# GCM_SCH_STM32.net
KiCad netlist of a schematic drawn in Altium Designer
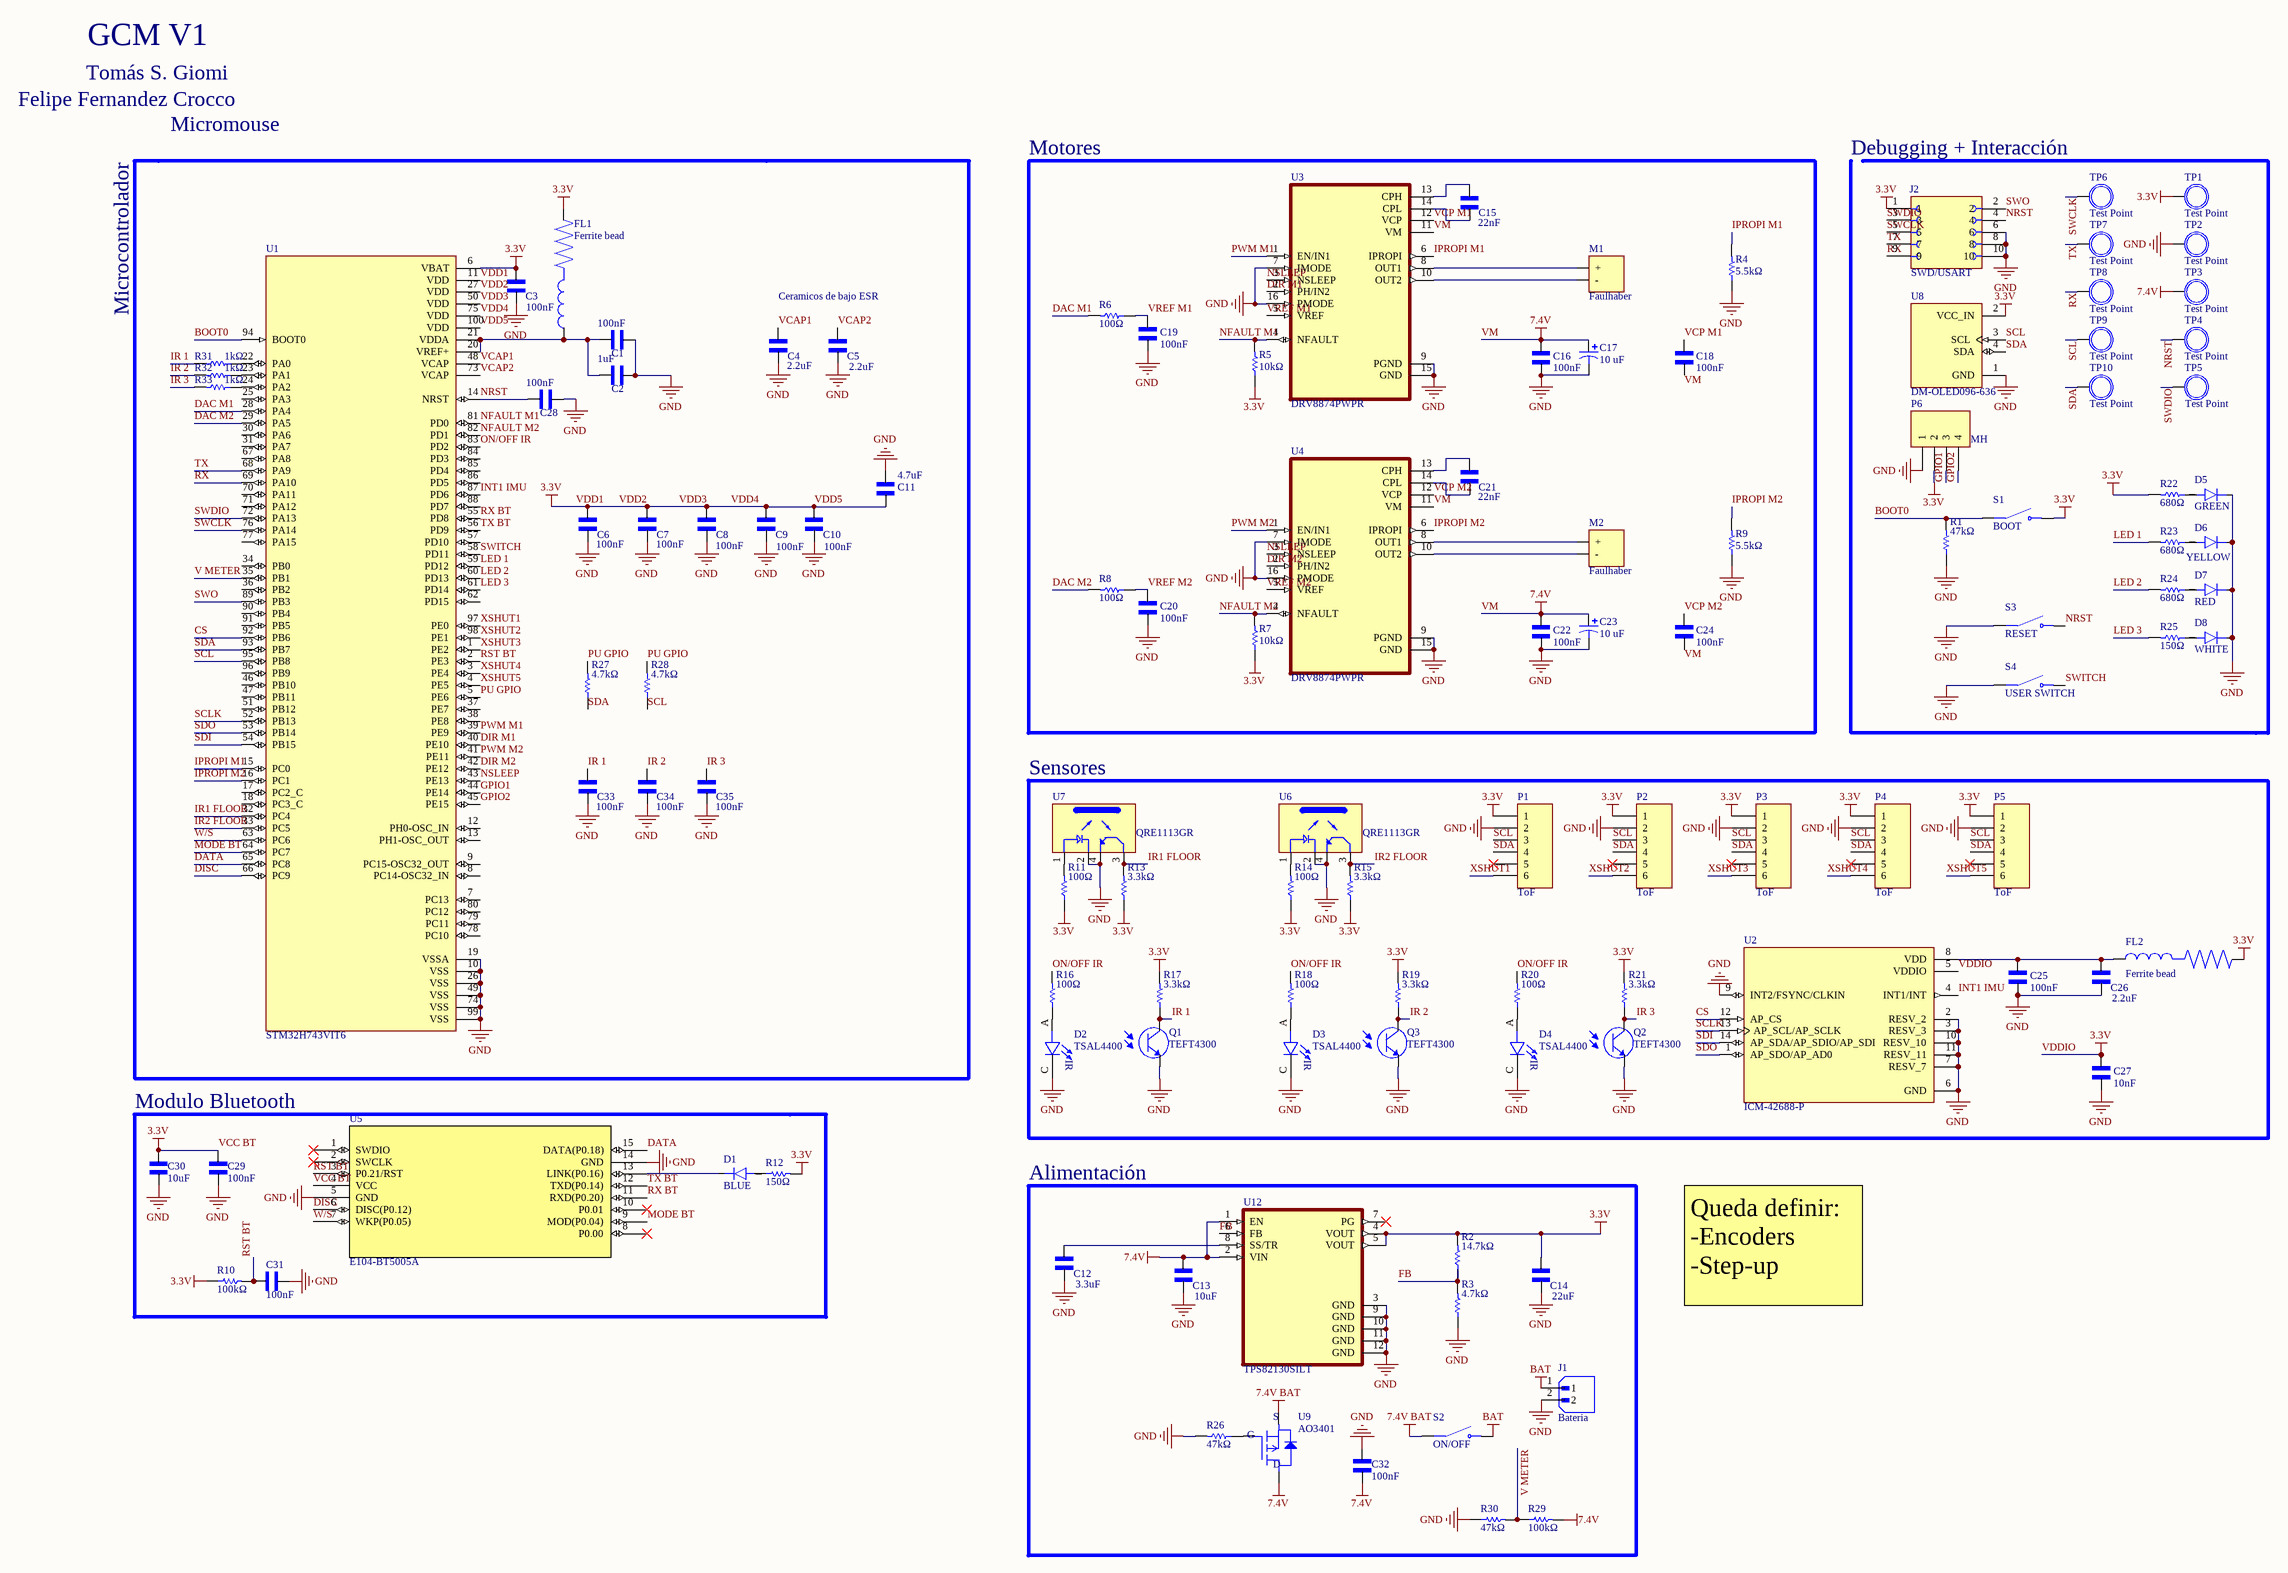
[diagram p0: GCM_SCH_STM32.SchDoc]

(export (version "E")
  (design (tool "Eeschema 10.0.6"))
  (components
    (comp (ref "C1")
      (value "100nF")
      (footprint "CAPACITOR TANTALIO")
      (description "0805")
      (fields (field (name "MP") "GRM035R60J475ME15D") (field (name "MF") "Murata"))
      (libsource (lib "") (part "CAPACITOR TANTALIO_1"))
    )
    (comp (ref "C2")
      (value "1uF")
      (footprint "CAPACITOR TANTALIO")
      (description "0805")
      (fields (field (name "MP") "GRM035R60J475ME15D") (field (name "MF") "Murata"))
      (libsource (lib "") (part "CAPACITOR TANTALIO_1"))
    )
    (comp (ref "C3")
      (value "100nF")
      (footprint "CAPACITOR TANTALIO")
      (description "0805")
      (fields (field (name "MP") "GRM035R60J475ME15D") (field (name "MF") "Murata"))
      (libsource (lib "GCMLibreriasSCH") (part "CAPACITOR TANTALIO"))
    )
    (comp (ref "C4")
      (value "2.2uF")
      (footprint "CAPACITOR TANTALIO")
      (description "0805")
      (fields (field (name "MP") "GRM035R60J475ME15D") (field (name "MF") "Murata"))
      (libsource (lib "GCMLibreriasSCH") (part "CAPACITOR TANTALIO"))
    )
    (comp (ref "C5")
      (value "2.2uF")
      (footprint "CAPACITOR TANTALIO")
      (description "0805")
      (fields (field (name "MP") "GRM035R60J475ME15D") (field (name "MF") "Murata"))
      (libsource (lib "GCMLibreriasSCH") (part "CAPACITOR TANTALIO"))
    )
    (comp (ref "C6")
      (value "100nF")
      (footprint "CAPACITOR TANTALIO")
      (description "0805")
      (fields (field (name "MP") "GRM035R60J475ME15D") (field (name "MF") "Murata"))
      (libsource (lib "GCMLibreriasSCH") (part "CAPACITOR TANTALIO"))
    )
    (comp (ref "C7")
      (value "100nF")
      (footprint "CAPACITOR TANTALIO")
      (description "0805")
      (fields (field (name "MP") "GRM035R60J475ME15D") (field (name "MF") "Murata"))
      (libsource (lib "GCMLibreriasSCH") (part "CAPACITOR TANTALIO"))
    )
    (comp (ref "C8")
      (value "100nF")
      (footprint "CAPACITOR TANTALIO")
      (description "0805")
      (fields (field (name "MP") "GRM035R60J475ME15D") (field (name "MF") "Murata"))
      (libsource (lib "GCMLibreriasSCH") (part "CAPACITOR TANTALIO"))
    )
    (comp (ref "C9")
      (value "100nF")
      (footprint "CAPACITOR TANTALIO")
      (description "0805")
      (fields (field (name "MP") "GRM035R60J475ME15D") (field (name "MF") "Murata"))
      (libsource (lib "GCMLibreriasSCH") (part "CAPACITOR TANTALIO"))
    )
    (comp (ref "C10")
      (value "100nF")
      (footprint "CAPACITOR TANTALIO")
      (description "0805")
      (fields (field (name "MP") "GRM035R60J475ME15D") (field (name "MF") "Murata"))
      (libsource (lib "GCMLibreriasSCH") (part "CAPACITOR TANTALIO"))
    )
    (comp (ref "C11")
      (value "4.7uF")
      (footprint "CAPACITOR TANTALIO")
      (description "0805")
      (fields (field (name "MP") "GRM035R60J475ME15D") (field (name "MF") "Murata"))
      (libsource (lib "GCMLibreriasSCH") (part "CAPACITOR TANTALIO"))
    )
    (comp (ref "C12")
      (value "3.3uF")
      (footprint "CAPACITOR TANTALIO")
      (description "0805")
      (fields (field (name "MP") "GRM035R60J475ME15D") (field (name "MF") "Murata"))
      (libsource (lib "GCMLibreriasSCH") (part "CAPACITOR TANTALIO"))
    )
    (comp (ref "C13")
      (value "10uF")
      (footprint "CAPACITOR TANTALIO")
      (description "0805")
      (fields (field (name "MP") "GRM035R60J475ME15D") (field (name "MF") "Murata"))
      (libsource (lib "GCMLibreriasSCH") (part "CAPACITOR TANTALIO"))
    )
    (comp (ref "C14")
      (value "22uF")
      (footprint "CAPACITOR TANTALIO")
      (description "0805")
      (fields (field (name "MP") "GRM035R60J475ME15D") (field (name "MF") "Murata"))
      (libsource (lib "GCMLibreriasSCH") (part "CAPACITOR TANTALIO"))
    )
    (comp (ref "C15")
      (value "22nF")
      (footprint "CAPACITOR TANTALIO")
      (description "0805")
      (fields (field (name "MP") "GRM035R60J475ME15D") (field (name "MF") "Murata"))
      (libsource (lib "GCMLibreriasSCH") (part "CAPACITOR TANTALIO"))
    )
    (comp (ref "C16")
      (value "100nF")
      (footprint "CAPACITOR TANTALIO")
      (description "0805")
      (fields (field (name "MP") "GRM035R60J475ME15D") (field (name "MF") "Murata"))
      (libsource (lib "GCMLibreriasSCH") (part "CAPACITOR TANTALIO"))
    )
    (comp (ref "C17")
      (value "10 uF")
      (footprint "Cap El 10uF")
      (libsource (lib "GCMLibreriasSCH") (part "Cap el 10 uF"))
    )
    (comp (ref "C18")
      (value "100nF")
      (footprint "CAPACITOR TANTALIO")
      (description "0805")
      (fields (field (name "MP") "GRM035R60J475ME15D") (field (name "MF") "Murata"))
      (libsource (lib "GCMLibreriasSCH") (part "CAPACITOR TANTALIO"))
    )
    (comp (ref "C19")
      (value "100nF")
      (footprint "CAPACITOR TANTALIO")
      (description "0805")
      (fields (field (name "MP") "GRM035R60J475ME15D") (field (name "MF") "Murata"))
      (libsource (lib "GCMLibreriasSCH") (part "CAPACITOR TANTALIO"))
    )
    (comp (ref "C20")
      (value "100nF")
      (footprint "CAPACITOR TANTALIO")
      (description "0805")
      (fields (field (name "MP") "GRM035R60J475ME15D") (field (name "MF") "Murata"))
      (libsource (lib "GCMLibreriasSCH") (part "CAPACITOR TANTALIO"))
    )
    (comp (ref "C21")
      (value "22nF")
      (footprint "CAPACITOR TANTALIO")
      (description "0805")
      (fields (field (name "MP") "GRM035R60J475ME15D") (field (name "MF") "Murata"))
      (libsource (lib "GCMLibreriasSCH") (part "CAPACITOR TANTALIO"))
    )
    (comp (ref "C22")
      (value "100nF")
      (footprint "CAPACITOR TANTALIO")
      (description "0805")
      (fields (field (name "MP") "GRM035R60J475ME15D") (field (name "MF") "Murata"))
      (libsource (lib "GCMLibreriasSCH") (part "CAPACITOR TANTALIO"))
    )
    (comp (ref "C23")
      (value "10 uF")
      (footprint "Cap El 10uF")
      (libsource (lib "GCMLibreriasSCH") (part "Cap el 10 uF"))
    )
    (comp (ref "C24")
      (value "100nF")
      (footprint "CAPACITOR TANTALIO")
      (description "0805")
      (fields (field (name "MP") "GRM035R60J475ME15D") (field (name "MF") "Murata"))
      (libsource (lib "GCMLibreriasSCH") (part "CAPACITOR TANTALIO"))
    )
    (comp (ref "C25")
      (value "100nF")
      (footprint "CAPACITOR TANTALIO")
      (description "0805")
      (fields (field (name "MP") "GRM035R60J475ME15D") (field (name "MF") "Murata"))
      (libsource (lib "GCMLibreriasSCH") (part "CAPACITOR TANTALIO"))
    )
    (comp (ref "C26")
      (value "2.2uF")
      (footprint "CAPACITOR TANTALIO")
      (description "0805")
      (fields (field (name "MP") "GRM035R60J475ME15D") (field (name "MF") "Murata"))
      (libsource (lib "GCMLibreriasSCH") (part "CAPACITOR TANTALIO"))
    )
    (comp (ref "C27")
      (value "10nF")
      (footprint "CAPACITOR TANTALIO")
      (description "0805")
      (fields (field (name "MP") "GRM035R60J475ME15D") (field (name "MF") "Murata"))
      (libsource (lib "GCMLibreriasSCH") (part "CAPACITOR TANTALIO"))
    )
    (comp (ref "C28")
      (value "100nF")
      (footprint "CAPACITOR TANTALIO")
      (description "0805")
      (fields (field (name "MP") "GRM035R60J475ME15D") (field (name "MF") "Murata"))
      (libsource (lib "") (part "CAPACITOR TANTALIO_1"))
    )
    (comp (ref "C29")
      (value "100nF")
      (footprint "CAPACITOR TANTALIO")
      (description "0805")
      (fields (field (name "MP") "GRM035R60J475ME15D") (field (name "MF") "Murata"))
      (libsource (lib "GCMLibreriasSCH") (part "CAPACITOR TANTALIO"))
    )
    (comp (ref "C30")
      (value "10uF")
      (footprint "CAPACITOR TANTALIO")
      (description "0805")
      (fields (field (name "MP") "GRM035R60J475ME15D") (field (name "MF") "Murata"))
      (libsource (lib "GCMLibreriasSCH") (part "CAPACITOR TANTALIO"))
    )
    (comp (ref "C31")
      (value "100nF")
      (footprint "CAPACITOR TANTALIO")
      (description "0805")
      (fields (field (name "MP") "GRM035R60J475ME15D") (field (name "MF") "Murata"))
      (libsource (lib "") (part "CAPACITOR TANTALIO_3"))
    )
    (comp (ref "C32")
      (value "100nF")
      (footprint "CAPACITOR TANTALIO")
      (description "0805")
      (fields (field (name "MP") "GRM035R60J475ME15D") (field (name "MF") "Murata"))
      (libsource (lib "") (part "CAPACITOR TANTALIO_2"))
    )
    (comp (ref "C33")
      (value "100nF")
      (footprint "CAPACITOR TANTALIO")
      (description "0805")
      (fields (field (name "MP") "GRM035R60J475ME15D") (field (name "MF") "Murata"))
      (libsource (lib "GCMLibreriasSCH") (part "CAPACITOR TANTALIO"))
    )
    (comp (ref "C34")
      (value "100nF")
      (footprint "CAPACITOR TANTALIO")
      (description "0805")
      (fields (field (name "MP") "GRM035R60J475ME15D") (field (name "MF") "Murata"))
      (libsource (lib "GCMLibreriasSCH") (part "CAPACITOR TANTALIO"))
    )
    (comp (ref "C35")
      (value "100nF")
      (footprint "CAPACITOR TANTALIO")
      (description "0805")
      (fields (field (name "MP") "GRM035R60J475ME15D") (field (name "MF") "Murata"))
      (libsource (lib "GCMLibreriasSCH") (part "CAPACITOR TANTALIO"))
    )
    (comp (ref "D1")
      (value "BLUE")
      (footprint "LED SMD")
      (description "0805")
      (fields (field (name "MP") "597-5311-402F"))
      (libsource (lib "GCMLibreriasSCH") (part "LED SMD"))
    )
    (comp (ref "D2")
      (value "TSAL4400")
      (footprint "GCMLibreriasPCB:LEDRD254W45D335H610")
      (description "Infrared Emitter 940nm 36mW/sr Circular Top Mount 2-Pin T-1 Bulk")
      (fields (field (name "MF") "Vishay Semiconductor"))
      (libsource (lib "GCMLibreriasSCH") (part "TSAL4400"))
    )
    (comp (ref "D3")
      (value "TSAL4400")
      (footprint "GCMLibreriasPCB:LEDRD254W45D335H610")
      (description "Infrared Emitter 940nm 36mW/sr Circular Top Mount 2-Pin T-1 Bulk")
      (fields (field (name "MF") "Vishay Semiconductor"))
      (libsource (lib "GCMLibreriasSCH") (part "TSAL4400"))
    )
    (comp (ref "D4")
      (value "TSAL4400")
      (footprint "GCMLibreriasPCB:LEDRD254W45D335H610")
      (description "Infrared Emitter 940nm 36mW/sr Circular Top Mount 2-Pin T-1 Bulk")
      (fields (field (name "MF") "Vishay Semiconductor"))
      (libsource (lib "GCMLibreriasSCH") (part "TSAL4400"))
    )
    (comp (ref "D5")
      (value "GREEN")
      (footprint "LED SMD")
      (description "0805")
      (fields (field (name "MP") "597-5311-402F"))
      (libsource (lib "GCMLibreriasSCH") (part "LED SMD"))
    )
    (comp (ref "D6")
      (value "YELLOW")
      (footprint "LED SMD")
      (description "0805")
      (fields (field (name "MP") "597-5311-402F"))
      (libsource (lib "GCMLibreriasSCH") (part "LED SMD"))
    )
    (comp (ref "D7")
      (value "RED")
      (footprint "LED SMD")
      (description "0805")
      (fields (field (name "MP") "597-5311-402F"))
      (libsource (lib "GCMLibreriasSCH") (part "LED SMD"))
    )
    (comp (ref "D8")
      (value "WHITE")
      (footprint "LED SMD")
      (description "0805")
      (fields (field (name "MP") "597-5311-402F"))
      (libsource (lib "GCMLibreriasSCH") (part "LED SMD"))
    )
    (comp (ref "FL1")
      (value "Ferrite bead")
      (footprint "BEADC1608X95N")
      (description "600 Ohms @ 100 MHz 1 - Ferrite Bead 0603 (1608 Metric) 500mA 380mOhm")
      (fields (field (name "MF") "Murata") (field (name "MP") "BLM18AG601SN1D"))
      (libsource (lib "GCMLibreriasSCH") (part "BLM18AG601SN1D"))
    )
    (comp (ref "FL2")
      (value "Ferrite bead")
      (footprint "BEADC1608X95N")
      (description "600 Ohms @ 100 MHz 1 - Ferrite Bead 0603 (1608 Metric) 500mA 380mOhm")
      (fields (field (name "MF") "Murata") (field (name "MP") "BLM18AG601SN1D"))
      (libsource (lib "GCMLibreriasSCH") (part "BLM18AG601SN1D"))
    )
    (comp (ref "J1")
      (value "Bateria")
      (footprint "JST_B2B-XH-A")
      (fields
        (field (name "MF") "{'manufacturer': u'JST Sales America Inc.'}")
        (field (name "MP") "B2B-XH-A")
      )
      (libsource (lib "GCMLibreriasSCH") (part "B2B-XH-A"))
    )
    (comp (ref "J2")
      (value "SWD/USART")
      (footprint "AMPHENOL_20021311-00026T4LF")
      (fields (field (name "MF") "Amphenol ICC") (field (name "MP") "20021311-00026T4LF"))
      (libsource (lib "GCMLibreriasSCH") (part "20021311-00026T4LF"))
    )
    (comp (ref "M1")
      (value "Faulhaber")
      (footprint "MOTOR")
      (fields (field (name "PUBLISHER") "Altium Limited"))
      (libsource (lib "GCMLibreriasSCH") (part "Faulhaber"))
    )
    (comp (ref "M2")
      (value "Faulhaber")
      (footprint "MOTOR")
      (fields (field (name "PUBLISHER") "Altium Limited"))
      (libsource (lib "GCMLibreriasSCH") (part "Faulhaber"))
    )
    (comp (ref "P1")
      (value "ToF")
      (footprint "FHDR1X6")
      (fields (field (name "PUBLISHER") "Altium Limited"))
      (libsource (lib "GCMLibreriasSCH") (part "FHeader 6X1"))
    )
    (comp (ref "P2")
      (value "ToF")
      (footprint "FHDR1X6")
      (fields (field (name "PUBLISHER") "Altium Limited"))
      (libsource (lib "GCMLibreriasSCH") (part "FHeader 6X1"))
    )
    (comp (ref "P3")
      (value "ToF")
      (footprint "FHDR1X6")
      (fields (field (name "PUBLISHER") "Altium Limited"))
      (libsource (lib "GCMLibreriasSCH") (part "FHeader 6X1"))
    )
    (comp (ref "P4")
      (value "ToF")
      (footprint "FHDR1X6")
      (fields (field (name "PUBLISHER") "Altium Limited"))
      (libsource (lib "GCMLibreriasSCH") (part "FHeader 6X1"))
    )
    (comp (ref "P5")
      (value "ToF")
      (footprint "FHDR1X6")
      (fields (field (name "PUBLISHER") "Altium Limited"))
      (libsource (lib "GCMLibreriasSCH") (part "FHeader 6X1"))
    )
    (comp (ref "P6")
      (value "MH")
      (footprint "FHDR1X4")
      (fields (field (name "PUBLISHER") "Altium Limited"))
      (libsource (lib "GCMLibreriasSCH") (part "FHeader 4X1_1"))
    )
    (comp (ref "Q1")
      (value "TEFT4300")
      (footprint "XDCR_TEFT4300")
      (description "Phototransistors 925nm Top View Radial, 3mm Dia (T-1)")
      (fields (field (name "MF") "Vishay Semiconductor"))
      (libsource (lib "GCMLibreriasSCH") (part "TEFT4300"))
    )
    (comp (ref "Q2")
      (value "TEFT4300")
      (footprint "XDCR_TEFT4300")
      (description "Phototransistors 925nm Top View Radial, 3mm Dia (T-1)")
      (fields (field (name "MF") "Vishay Semiconductor"))
      (libsource (lib "GCMLibreriasSCH") (part "TEFT4300"))
    )
    (comp (ref "Q3")
      (value "TEFT4300")
      (footprint "XDCR_TEFT4300")
      (description "Phototransistors 925nm Top View Radial, 3mm Dia (T-1)")
      (fields (field (name "MF") "Vishay Semiconductor"))
      (libsource (lib "GCMLibreriasSCH") (part "TEFT4300"))
    )
    (comp (ref "R1")
      (value "47kΩ")
      (footprint "RESISTENCIA SMD")
      (description "0805")
      (fields (field (name "PUBLISHER") "Altium Limited"))
      (libsource (lib "GCMLibreriasSCH") (part "RESISTENCIA"))
    )
    (comp (ref "R2")
      (value "14.7kΩ")
      (footprint "RESISTENCIA SMD")
      (description "0805")
      (fields (field (name "PUBLISHER") "Altium Limited"))
      (libsource (lib "GCMLibreriasSCH") (part "RESISTENCIA"))
    )
    (comp (ref "R3")
      (value "4.7kΩ")
      (footprint "RESISTENCIA SMD")
      (description "0805")
      (fields (field (name "PUBLISHER") "Altium Limited"))
      (libsource (lib "GCMLibreriasSCH") (part "RESISTENCIA"))
    )
    (comp (ref "R4")
      (value "5.5kΩ")
      (footprint "RESISTENCIA SMD")
      (description "0805")
      (fields (field (name "PUBLISHER") "Altium Limited"))
      (libsource (lib "GCMLibreriasSCH") (part "RESISTENCIA"))
    )
    (comp (ref "R5")
      (value "10kΩ")
      (footprint "RESISTENCIA SMD")
      (description "0805")
      (fields (field (name "PUBLISHER") "Altium Limited"))
      (libsource (lib "GCMLibreriasSCH") (part "RESISTENCIA"))
    )
    (comp (ref "R6")
      (value "100Ω")
      (footprint "RESISTENCIA SMD")
      (description "0805")
      (fields (field (name "PUBLISHER") "Altium Limited"))
      (libsource (lib "GCMLibreriasSCH") (part "RESISTENCIA"))
    )
    (comp (ref "R7")
      (value "10kΩ")
      (footprint "RESISTENCIA SMD")
      (description "0805")
      (fields (field (name "PUBLISHER") "Altium Limited"))
      (libsource (lib "GCMLibreriasSCH") (part "RESISTENCIA"))
    )
    (comp (ref "R8")
      (value "100Ω")
      (footprint "RESISTENCIA SMD")
      (description "0805")
      (fields (field (name "PUBLISHER") "Altium Limited"))
      (libsource (lib "GCMLibreriasSCH") (part "RESISTENCIA"))
    )
    (comp (ref "R9")
      (value "5.5kΩ")
      (footprint "RESISTENCIA SMD")
      (description "0805")
      (fields (field (name "PUBLISHER") "Altium Limited"))
      (libsource (lib "GCMLibreriasSCH") (part "RESISTENCIA"))
    )
    (comp (ref "R10")
      (value "100kΩ")
      (footprint "RESISTENCIA SMD")
      (description "0805")
      (fields (field (name "PUBLISHER") "Altium Limited"))
      (libsource (lib "GCMLibreriasSCH") (part "RESISTENCIA"))
    )
    (comp (ref "R11")
      (value "100Ω")
      (footprint "RESISTENCIA SMD")
      (description "0805")
      (fields (field (name "PUBLISHER") "Altium Limited"))
      (libsource (lib "GCMLibreriasSCH") (part "RESISTENCIA"))
    )
    (comp (ref "R12")
      (value "150Ω")
      (footprint "RESISTENCIA SMD")
      (description "0805")
      (fields (field (name "PUBLISHER") "Altium Limited"))
      (libsource (lib "GCMLibreriasSCH") (part "RESISTENCIA"))
    )
    (comp (ref "R13")
      (value "3.3kΩ")
      (footprint "RESISTENCIA SMD")
      (description "0805")
      (fields (field (name "PUBLISHER") "Altium Limited"))
      (libsource (lib "GCMLibreriasSCH") (part "RESISTENCIA"))
    )
    (comp (ref "R14")
      (value "100Ω")
      (footprint "RESISTENCIA SMD")
      (description "0805")
      (fields (field (name "PUBLISHER") "Altium Limited"))
      (libsource (lib "GCMLibreriasSCH") (part "RESISTENCIA"))
    )
    (comp (ref "R15")
      (value "3.3kΩ")
      (footprint "RESISTENCIA SMD")
      (description "0805")
      (fields (field (name "PUBLISHER") "Altium Limited"))
      (libsource (lib "GCMLibreriasSCH") (part "RESISTENCIA"))
    )
    (comp (ref "R16")
      (value "100Ω")
      (footprint "RESISTENCIA SMD")
      (description "0805")
      (fields (field (name "PUBLISHER") "Altium Limited"))
      (libsource (lib "GCMLibreriasSCH") (part "RESISTENCIA"))
    )
    (comp (ref "R17")
      (value "3.3kΩ")
      (footprint "RESISTENCIA SMD")
      (description "0805")
      (fields (field (name "PUBLISHER") "Altium Limited"))
      (libsource (lib "GCMLibreriasSCH") (part "RESISTENCIA"))
    )
    (comp (ref "R18")
      (value "100Ω")
      (footprint "RESISTENCIA SMD")
      (description "0805")
      (fields (field (name "PUBLISHER") "Altium Limited"))
      (libsource (lib "GCMLibreriasSCH") (part "RESISTENCIA"))
    )
    (comp (ref "R19")
      (value "3.3kΩ")
      (footprint "RESISTENCIA SMD")
      (description "0805")
      (fields (field (name "PUBLISHER") "Altium Limited"))
      (libsource (lib "GCMLibreriasSCH") (part "RESISTENCIA"))
    )
    (comp (ref "R20")
      (value "100Ω")
      (footprint "RESISTENCIA SMD")
      (description "0805")
      (fields (field (name "PUBLISHER") "Altium Limited"))
      (libsource (lib "GCMLibreriasSCH") (part "RESISTENCIA"))
    )
    (comp (ref "R21")
      (value "3.3kΩ")
      (footprint "RESISTENCIA SMD")
      (description "0805")
      (fields (field (name "PUBLISHER") "Altium Limited"))
      (libsource (lib "GCMLibreriasSCH") (part "RESISTENCIA"))
    )
    (comp (ref "R22")
      (value "680Ω")
      (footprint "RESISTENCIA SMD")
      (description "0805")
      (fields (field (name "PUBLISHER") "Altium Limited"))
      (libsource (lib "GCMLibreriasSCH") (part "RESISTENCIA"))
    )
    (comp (ref "R23")
      (value "680Ω")
      (footprint "RESISTENCIA SMD")
      (description "0805")
      (fields (field (name "PUBLISHER") "Altium Limited"))
      (libsource (lib "GCMLibreriasSCH") (part "RESISTENCIA"))
    )
    (comp (ref "R24")
      (value "680Ω")
      (footprint "RESISTENCIA SMD")
      (description "0805")
      (fields (field (name "PUBLISHER") "Altium Limited"))
      (libsource (lib "GCMLibreriasSCH") (part "RESISTENCIA"))
    )
    (comp (ref "R25")
      (value "150Ω")
      (footprint "RESISTENCIA SMD")
      (description "0805")
      (fields (field (name "PUBLISHER") "Altium Limited"))
      (libsource (lib "GCMLibreriasSCH") (part "RESISTENCIA"))
    )
    (comp (ref "R26")
      (value "47kΩ")
      (footprint "RESISTENCIA SMD")
      (description "0805")
      (fields (field (name "PUBLISHER") "Altium Limited"))
      (libsource (lib "GCMLibreriasSCH") (part "RESISTENCIA"))
    )
    (comp (ref "R27")
      (value "4.7kΩ")
      (footprint "RESISTENCIA SMD")
      (description "0805")
      (fields (field (name "PUBLISHER") "Altium Limited"))
      (libsource (lib "GCMLibreriasSCH") (part "RESISTENCIA"))
    )
    (comp (ref "R28")
      (value "4.7kΩ")
      (footprint "RESISTENCIA SMD")
      (description "0805")
      (fields (field (name "PUBLISHER") "Altium Limited"))
      (libsource (lib "GCMLibreriasSCH") (part "RESISTENCIA"))
    )
    (comp (ref "R29")
      (value "100kΩ")
      (footprint "RESISTENCIA SMD")
      (description "0805")
      (fields (field (name "PUBLISHER") "Altium Limited"))
      (libsource (lib "GCMLibreriasSCH") (part "RESISTENCIA"))
    )
    (comp (ref "R30")
      (value "47kΩ")
      (footprint "RESISTENCIA SMD")
      (description "0805")
      (fields (field (name "PUBLISHER") "Altium Limited"))
      (libsource (lib "GCMLibreriasSCH") (part "RESISTENCIA"))
    )
    (comp (ref "R31")
      (value "1kΩ")
      (footprint "RESISTENCIA SMD")
      (description "0805")
      (fields (field (name "PUBLISHER") "Altium Limited"))
      (libsource (lib "GCMLibreriasSCH") (part "RESISTENCIA"))
    )
    (comp (ref "R32")
      (value "1kΩ")
      (footprint "RESISTENCIA SMD")
      (description "0805")
      (fields (field (name "PUBLISHER") "Altium Limited"))
      (libsource (lib "GCMLibreriasSCH") (part "RESISTENCIA"))
    )
    (comp (ref "R33")
      (value "1kΩ")
      (footprint "RESISTENCIA SMD")
      (description "0805")
      (fields (field (name "PUBLISHER") "Altium Limited"))
      (libsource (lib "GCMLibreriasSCH") (part "RESISTENCIA"))
    )
    (comp (ref "S1")
      (value "BOOT")
      (footprint "SW_TS09-63-25-WT-160-SMT-TR")
      (description "6.1 x 3.7 mm, 2.5 mm Actuator Height, 160 gf, White, Surface Mount, SPST, Tactile Switch")
      (fields (field (name "MF") "Same Sky") (field (name "MP") "TS09-63-25-WT-160-SMT-TR"))
      (libsource (lib "GCMLibreriasSCH") (part "TS09-63-25-WT-160-SMT-TR"))
    )
    (comp (ref "S2")
      (value "ON/OFF")
      (footprint "SW_L101011ML04Q")
      (description "Switch Slide ON OFF SPST Side Slide 4A 250VAC 125VDC PC Pins Thru-Hole Bulk")
      (fields (field (name "MF") "C&K") (field (name "MP") "L101011ML04Q"))
      (libsource (lib "GCMLibreriasSCH") (part "L101011ML04Q"))
    )
    (comp (ref "S3")
      (value "RESET")
      (footprint "SW_TS09-63-25-WT-160-SMT-TR")
      (description "6.1 x 3.7 mm, 2.5 mm Actuator Height, 160 gf, White, Surface Mount, SPST, Tactile Switch")
      (fields (field (name "MF") "Same Sky") (field (name "MP") "TS09-63-25-WT-160-SMT-TR"))
      (libsource (lib "GCMLibreriasSCH") (part "TS09-63-25-WT-160-SMT-TR"))
    )
    (comp (ref "S4")
      (value "USER SWITCH")
      (footprint "SW_TS09-63-25-WT-160-SMT-TR")
      (description "6.1 x 3.7 mm, 2.5 mm Actuator Height, 160 gf, White, Surface Mount, SPST, Tactile Switch")
      (fields (field (name "MF") "Same Sky") (field (name "MP") "TS09-63-25-WT-160-SMT-TR"))
      (libsource (lib "GCMLibreriasSCH") (part "TS09-63-25-WT-160-SMT-TR"))
    )
    (comp (ref "TP1")
      (value "Test Point")
      (footprint "TestPoint")
      (libsource (lib "GCMLibreriasSCH") (part "Test Point"))
    )
    (comp (ref "TP2")
      (value "Test Point")
      (footprint "TestPoint")
      (libsource (lib "GCMLibreriasSCH") (part "Test Point"))
    )
    (comp (ref "TP3")
      (value "Test Point")
      (footprint "TestPoint")
      (libsource (lib "GCMLibreriasSCH") (part "Test Point"))
    )
    (comp (ref "TP4")
      (value "Test Point")
      (footprint "TestPoint")
      (libsource (lib "GCMLibreriasSCH") (part "Test Point"))
    )
    (comp (ref "TP5")
      (value "Test Point")
      (footprint "TestPoint")
      (libsource (lib "GCMLibreriasSCH") (part "Test Point"))
    )
    (comp (ref "TP6")
      (value "Test Point")
      (footprint "TestPoint")
      (libsource (lib "GCMLibreriasSCH") (part "Test Point"))
    )
    (comp (ref "TP7")
      (value "Test Point")
      (footprint "TestPoint")
      (libsource (lib "GCMLibreriasSCH") (part "Test Point"))
    )
    (comp (ref "TP8")
      (value "Test Point")
      (footprint "TestPoint")
      (libsource (lib "GCMLibreriasSCH") (part "Test Point"))
    )
    (comp (ref "TP9")
      (value "Test Point")
      (footprint "TestPoint")
      (libsource (lib "GCMLibreriasSCH") (part "Test Point"))
    )
    (comp (ref "TP10")
      (value "Test Point")
      (footprint "TestPoint")
      (libsource (lib "GCMLibreriasSCH") (part "Test Point"))
    )
    (comp (ref "U1")
      (value "STM32H743VIT6")
      (footprint "QFP50P1600X1600X160-100N")
      (fields (field (name "MF") "STMicroelectronics"))
      (libsource (lib "GCMLibreriasSCH") (part "STM32H743VIT6"))
    )
    (comp (ref "U2")
      (value "ICM-42688-P")
      (footprint "GCMLibreriasPCB:PQFN50P300X250X97-14N")
      (description "Accelerometer, Gyroscope, 6 Axis Sensor Output")
      (libsource (lib "GCMLibreriasSCH") (part "ICM-42688-P"))
    )
    (comp (ref "U3")
      (value "DRV8874PWPR")
      (footprint "SOP65P640X120-17N")
      (description "40-V, 6-A H-bridge motor driver with integrated current sensing feedback")
      (fields (field (name "MF") "Texas Instruments"))
      (libsource (lib "GCMLibreriasSCH") (part "DRV8874PWPR"))
    )
    (comp (ref "U4")
      (value "DRV8874PWPR")
      (footprint "SOP65P640X120-17N")
      (description "40-V, 6-A H-bridge motor driver with integrated current sensing feedback")
      (fields (field (name "MF") "Texas Instruments"))
      (libsource (lib "GCMLibreriasSCH") (part "DRV8874PWPR"))
    )
    (comp (ref "U5")
      (value "E104-BT5005A")
      (footprint "MOD15_E104-BT5005A_BYT")
      (description "No Description Available")
      (fields (field (name "COPYRIGHT") "Copyright (C) 2026 Ultra Librarian. All rights reserved."))
      (libsource (lib "GCMLibreriasSCH") (part "E104-BT5005A"))
    )
    (comp (ref "U6")
      (value "QRE1113GR")
      (footprint "SOIC180P460X187-4N")
      (description "Reflective Optical Sensor 0.039 (1mm) 4-SMD, Gull Wing")
      (fields (field (name "MF") "ON Semiconductor"))
      (libsource (lib "GCMLibreriasSCH") (part "QRE1113GR"))
    )
    (comp (ref "U7")
      (value "QRE1113GR")
      (footprint "SOIC180P460X187-4N")
      (description "Reflective Optical Sensor 0.039 (1mm) 4-SMD, Gull Wing")
      (fields (field (name "MF") "ON Semiconductor"))
      (libsource (lib "GCMLibreriasSCH") (part "QRE1113GR"))
    )
    (comp (ref "U8")
      (value "DM-OLED096-636")
      (footprint "MODULE_DM-OLED096-636")
      (description "0.96â€ 128 X 64 MONOCHROME GRAPHIC OLED DISPLAY MODULE - I2C")
      (fields (field (name "MF") "Display Module"))
      (libsource (lib "GCMLibreriasSCH") (part "DM-OLED096-636"))
    )
    (comp (ref "U9")
      (value "AO3401")
      (footprint "SOT23")
      (description "P-Channel 30 V 4A (Ta) 1.4W (Ta) Surface Mount SOT-23-3")
      (fields (field (name "MF") "Alpha & Omega Semiconductor"))
      (libsource (lib "GCMLibreriasSCH") (part "AO3401"))
    )
    (comp (ref "U12")
      (value "TPS82130SILT")
      (footprint "CONV_TPS82140SILR")
      (description "Non-Isolated PoL Module DC DC Converter 1 Output 0.9 ~ 5V - - - 3A 3V - 17V Input")
      (fields (field (name "MF") "Texas Instruments") (field (name "MP") "TPS82130SIL"))
      (libsource (lib "GCMLibreriasSCH") (part "TPS82130SILT"))
    )
  )
  (nets
    (net (code "1") (name "/BOOT0") (class "Default")
      (node (ref "R1") (pin "2") (pinfunction "2_2") (pintype "passive"))
      (node (ref "S1") (pin "1") (pinfunction "1_1") (pintype "passive"))
      (node (ref "U1") (pin "94") (pinfunction "BOOT0_94") (pintype "input"))
    )
    (net (code "2") (name "/CS") (class "Default")
      (node (ref "U1") (pin "92") (pinfunction "PB6_92") (pintype "bidirectional"))
      (node (ref "U2") (pin "12") (pinfunction "AP_CS_12") (pintype "input"))
    )
    (net (code "3") (name "/DAC M1") (class "Default")
      (node (ref "R6") (pin "2") (pinfunction "2_2") (pintype "passive"))
      (node (ref "U1") (pin "28") (pinfunction "PA4_28") (pintype "bidirectional"))
    )
    (net (code "4") (name "/DAC M2") (class "Default")
      (node (ref "R8") (pin "2") (pinfunction "2_2") (pintype "passive"))
      (node (ref "U1") (pin "29") (pinfunction "PA5_29") (pintype "bidirectional"))
    )
    (net (code "5") (name "/DATA") (class "Default")
      (node (ref "U1") (pin "65") (pinfunction "PC8_65") (pintype "bidirectional"))
      (node (ref "U5") (pin "15") (pinfunction "DATA(P0.18)_15") (pintype "bidirectional"))
    )
    (net (code "6") (name "/DIR M1") (class "Default")
      (node (ref "U1") (pin "40") (pinfunction "PE10_40") (pintype "bidirectional"))
      (node (ref "U3") (pin "2") (pinfunction "PH/IN2_2") (pintype "input"))
    )
    (net (code "7") (name "/DIR M2") (class "Default")
      (node (ref "U1") (pin "42") (pinfunction "PE12_42") (pintype "bidirectional"))
      (node (ref "U4") (pin "2") (pinfunction "PH/IN2_2") (pintype "input"))
    )
    (net (code "8") (name "/DISC") (class "Default")
      (node (ref "U1") (pin "66") (pinfunction "PC9_66") (pintype "bidirectional"))
      (node (ref "U5") (pin "6") (pinfunction "DISC(P0.12)_6") (pintype "bidirectional"))
    )
    (net (code "9") (name "/FB") (class "Default")
      (node (ref "R2") (pin "1") (pinfunction "1_1") (pintype "passive"))
      (node (ref "R3") (pin "2") (pinfunction "2_2") (pintype "passive"))
      (node (ref "U12") (pin "6") (pinfunction "FB_6") (pintype "input"))
    )
    (net (code "10") (name "/GPIO1") (class "Default")
      (node (ref "P6") (pin "3") (pinfunction "3_3") (pintype "passive"))
      (node (ref "U1") (pin "44") (pinfunction "PE14_44") (pintype "bidirectional"))
    )
    (net (code "11") (name "/GPIO2") (class "Default")
      (node (ref "P6") (pin "4") (pinfunction "4_4") (pintype "passive"))
      (node (ref "U1") (pin "45") (pinfunction "PE15_45") (pintype "bidirectional"))
    )
    (net (code "12") (name "/INT1 IMU") (class "Default")
      (node (ref "U1") (pin "87") (pinfunction "PD6_87") (pintype "bidirectional"))
      (node (ref "U2") (pin "4") (pinfunction "INT1/INT_4") (pintype "output"))
    )
    (net (code "13") (name "/IPROPI M1") (class "Default")
      (node (ref "R4") (pin "2") (pinfunction "2_2") (pintype "passive"))
      (node (ref "U1") (pin "15") (pinfunction "PC0_15") (pintype "bidirectional"))
      (node (ref "U3") (pin "6") (pinfunction "IPROPI_6") (pintype "output"))
    )
    (net (code "14") (name "/IPROPI M2") (class "Default")
      (node (ref "R9") (pin "2") (pinfunction "2_2") (pintype "passive"))
      (node (ref "U1") (pin "16") (pinfunction "PC1_16") (pintype "bidirectional"))
      (node (ref "U4") (pin "6") (pinfunction "IPROPI_6") (pintype "output"))
    )
    (net (code "15") (name "/IR 1") (class "Default")
      (node (ref "C33") (pin "2") (pinfunction "2_2") (pintype "passive"))
      (node (ref "Q1") (pin "C") (pinfunction "C_C") (pintype "passive"))
      (node (ref "R17") (pin "1") (pinfunction "1_1") (pintype "passive"))
      (node (ref "R31") (pin "2") (pinfunction "2_2") (pintype "passive"))
    )
    (net (code "16") (name "/IR 2") (class "Default")
      (node (ref "C34") (pin "2") (pinfunction "2_2") (pintype "passive"))
      (node (ref "Q3") (pin "C") (pinfunction "C_C") (pintype "passive"))
      (node (ref "R19") (pin "1") (pinfunction "1_1") (pintype "passive"))
      (node (ref "R32") (pin "2") (pinfunction "2_2") (pintype "passive"))
    )
    (net (code "17") (name "/IR 3") (class "Default")
      (node (ref "C35") (pin "2") (pinfunction "2_2") (pintype "passive"))
      (node (ref "Q2") (pin "C") (pinfunction "C_C") (pintype "passive"))
      (node (ref "R21") (pin "1") (pinfunction "1_1") (pintype "passive"))
      (node (ref "R33") (pin "2") (pinfunction "2_2") (pintype "passive"))
    )
    (net (code "18") (name "/IR1 FLOOR") (class "Default")
      (node (ref "R13") (pin "2") (pinfunction "2_2") (pintype "passive"))
      (node (ref "U1") (pin "32") (pinfunction "PC4_32") (pintype "bidirectional"))
      (node (ref "U7") (pin "3") (pinfunction "CT_3") (pintype "passive"))
    )
    (net (code "19") (name "/IR2 FLOOR") (class "Default")
      (node (ref "R15") (pin "2") (pinfunction "2_2") (pintype "passive"))
      (node (ref "U1") (pin "33") (pinfunction "PC5_33") (pintype "bidirectional"))
      (node (ref "U6") (pin "3") (pinfunction "CT_3") (pintype "passive"))
    )
    (net (code "20") (name "/LED 1") (class "Default")
      (node (ref "R23") (pin "2") (pinfunction "2_2") (pintype "passive"))
      (node (ref "U1") (pin "59") (pinfunction "PD12_59") (pintype "bidirectional"))
    )
    (net (code "21") (name "/LED 2") (class "Default")
      (node (ref "R24") (pin "2") (pinfunction "2_2") (pintype "passive"))
      (node (ref "U1") (pin "60") (pinfunction "PD13_60") (pintype "bidirectional"))
    )
    (net (code "22") (name "/LED 3") (class "Default")
      (node (ref "R25") (pin "2") (pinfunction "2_2") (pintype "passive"))
      (node (ref "U1") (pin "61") (pinfunction "PD14_61") (pintype "bidirectional"))
    )
    (net (code "23") (name "/MODE BT") (class "Default")
      (node (ref "U1") (pin "64") (pinfunction "PC7_64") (pintype "bidirectional"))
      (node (ref "U5") (pin "9") (pinfunction "MOD(P0.04)_9") (pintype "bidirectional"))
    )
    (net (code "24") (name "/NFAULT M1") (class "Default")
      (node (ref "R5") (pin "2") (pinfunction "2_2") (pintype "passive"))
      (node (ref "U1") (pin "81") (pinfunction "PD0_81") (pintype "bidirectional"))
      (node (ref "U3") (pin "4") (pinfunction "NFAULT_4") (pintype "bidirectional"))
    )
    (net (code "25") (name "/NFAULT M2") (class "Default")
      (node (ref "R7") (pin "2") (pinfunction "2_2") (pintype "passive"))
      (node (ref "U1") (pin "82") (pinfunction "PD1_82") (pintype "bidirectional"))
      (node (ref "U4") (pin "4") (pinfunction "NFAULT_4") (pintype "bidirectional"))
    )
    (net (code "26") (name "/NRST") (class "Default")
      (node (ref "C28") (pin "1") (pinfunction "1_1") (pintype "passive"))
      (node (ref "J2") (pin "4") (pinfunction "4_4") (pintype "passive"))
      (node (ref "S3") (pin "2") (pinfunction "2_2") (pintype "passive"))
      (node (ref "TP4") (pin "1") (pinfunction "1_1") (pintype "passive"))
      (node (ref "U1") (pin "14") (pinfunction "NRST_14") (pintype "bidirectional"))
    )
    (net (code "27") (name "/NSLEEP") (class "Default")
      (node (ref "U1") (pin "43") (pinfunction "PE13_43") (pintype "bidirectional"))
      (node (ref "U3") (pin "3") (pinfunction "NSLEEP_3") (pintype "input"))
      (node (ref "U4") (pin "3") (pinfunction "NSLEEP_3") (pintype "input"))
    )
    (net (code "28") (name "/ON{slash}OFF IR") (class "Default")
      (node (ref "R16") (pin "2") (pinfunction "2_2") (pintype "passive"))
      (node (ref "R18") (pin "2") (pinfunction "2_2") (pintype "passive"))
      (node (ref "R20") (pin "2") (pinfunction "2_2") (pintype "passive"))
      (node (ref "U1") (pin "83") (pinfunction "PD2_83") (pintype "bidirectional"))
    )
    (net (code "29") (name "/PU GPIO") (class "Default")
      (node (ref "R27") (pin "2") (pinfunction "2_2") (pintype "passive"))
      (node (ref "R28") (pin "2") (pinfunction "2_2") (pintype "passive"))
      (node (ref "U1") (pin "5") (pinfunction "PE6_5") (pintype "bidirectional"))
    )
    (net (code "30") (name "/PWM M1") (class "Default")
      (node (ref "U1") (pin "39") (pinfunction "PE9_39") (pintype "bidirectional"))
      (node (ref "U3") (pin "1") (pinfunction "EN/IN1_1") (pintype "input"))
    )
    (net (code "31") (name "/PWM M2") (class "Default")
      (node (ref "U1") (pin "41") (pinfunction "PE11_41") (pintype "bidirectional"))
      (node (ref "U4") (pin "1") (pinfunction "EN/IN1_1") (pintype "input"))
    )
    (net (code "32") (name "/RST BT") (class "Default")
      (node (ref "C31") (pin "2") (pinfunction "2_2") (pintype "passive"))
      (node (ref "R10") (pin "2") (pinfunction "2_2") (pintype "passive"))
      (node (ref "U1") (pin "2") (pinfunction "PE3_2") (pintype "bidirectional"))
      (node (ref "U5") (pin "3") (pinfunction "P0.21/RST_3") (pintype "bidirectional"))
    )
    (net (code "33") (name "/RX") (class "Default")
      (node (ref "J2") (pin "9") (pinfunction "9_9") (pintype "passive"))
      (node (ref "TP8") (pin "1") (pinfunction "1_1") (pintype "passive"))
      (node (ref "U1") (pin "69") (pinfunction "PA10_69") (pintype "bidirectional"))
    )
    (net (code "34") (name "/RX BT") (class "Default")
      (node (ref "U1") (pin "55") (pinfunction "PD8_55") (pintype "bidirectional"))
      (node (ref "U5") (pin "11") (pinfunction "RXD(P0.20)_11") (pintype "bidirectional"))
    )
    (net (code "35") (name "/SCL") (class "Default")
      (node (ref "P1") (pin "3") (pinfunction "3_3") (pintype "passive"))
      (node (ref "P2") (pin "3") (pinfunction "3_3") (pintype "passive"))
      (node (ref "P3") (pin "3") (pinfunction "3_3") (pintype "passive"))
      (node (ref "P4") (pin "3") (pinfunction "3_3") (pintype "passive"))
      (node (ref "P5") (pin "3") (pinfunction "3_3") (pintype "passive"))
      (node (ref "R28") (pin "1") (pinfunction "1_1") (pintype "passive"))
      (node (ref "TP9") (pin "1") (pinfunction "1_1") (pintype "passive"))
      (node (ref "U1") (pin "95") (pinfunction "PB8_95") (pintype "bidirectional"))
      (node (ref "U8") (pin "3") (pinfunction "SCL_3") (pintype "input"))
    )
    (net (code "36") (name "/SCLK") (class "Default")
      (node (ref "U1") (pin "52") (pinfunction "PB13_52") (pintype "bidirectional"))
      (node (ref "U2") (pin "13") (pinfunction "AP_SCL/AP_SCLK_13") (pintype "input"))
    )
    (net (code "37") (name "/SDA") (class "Default")
      (node (ref "P1") (pin "4") (pinfunction "4_4") (pintype "passive"))
      (node (ref "P2") (pin "4") (pinfunction "4_4") (pintype "passive"))
      (node (ref "P3") (pin "4") (pinfunction "4_4") (pintype "passive"))
      (node (ref "P4") (pin "4") (pinfunction "4_4") (pintype "passive"))
      (node (ref "P5") (pin "4") (pinfunction "4_4") (pintype "passive"))
      (node (ref "R27") (pin "1") (pinfunction "1_1") (pintype "passive"))
      (node (ref "TP10") (pin "1") (pinfunction "1_1") (pintype "passive"))
      (node (ref "U1") (pin "93") (pinfunction "PB7_93") (pintype "bidirectional"))
      (node (ref "U8") (pin "4") (pinfunction "SDA_4") (pintype "bidirectional"))
    )
    (net (code "38") (name "/SDI") (class "Default")
      (node (ref "U1") (pin "54") (pinfunction "PB15_54") (pintype "bidirectional"))
      (node (ref "U2") (pin "14") (pinfunction "AP_SDA/AP_SDIO/AP_SDI_14") (pintype "bidirectional"))
    )
    (net (code "39") (name "/SDO") (class "Default")
      (node (ref "U1") (pin "53") (pinfunction "PB14_53") (pintype "bidirectional"))
      (node (ref "U2") (pin "1") (pinfunction "AP_SDO/AP_AD0_1") (pintype "bidirectional"))
    )
    (net (code "40") (name "/SWCLK") (class "Default")
      (node (ref "J2") (pin "5") (pinfunction "5_5") (pintype "passive"))
      (node (ref "TP6") (pin "1") (pinfunction "1_1") (pintype "passive"))
      (node (ref "U1") (pin "76") (pinfunction "PA14_76") (pintype "bidirectional"))
    )
    (net (code "41") (name "/SWDIO") (class "Default")
      (node (ref "J2") (pin "3") (pinfunction "3_3") (pintype "passive"))
      (node (ref "TP5") (pin "1") (pinfunction "1_1") (pintype "passive"))
      (node (ref "U1") (pin "72") (pinfunction "PA13_72") (pintype "bidirectional"))
    )
    (net (code "42") (name "/SWITCH") (class "Default")
      (node (ref "S4") (pin "2") (pinfunction "2_2") (pintype "passive"))
      (node (ref "U1") (pin "58") (pinfunction "PD11_58") (pintype "bidirectional"))
    )
    (net (code "43") (name "/SWO") (class "Default")
      (node (ref "J2") (pin "2") (pinfunction "2_2") (pintype "passive"))
      (node (ref "U1") (pin "89") (pinfunction "PB3_89") (pintype "bidirectional"))
    )
    (net (code "44") (name "/TX") (class "Default")
      (node (ref "J2") (pin "7") (pinfunction "7_7") (pintype "passive"))
      (node (ref "TP7") (pin "1") (pinfunction "1_1") (pintype "passive"))
      (node (ref "U1") (pin "68") (pinfunction "PA9_68") (pintype "bidirectional"))
    )
    (net (code "45") (name "/TX BT") (class "Default")
      (node (ref "U1") (pin "56") (pinfunction "PD9_56") (pintype "bidirectional"))
      (node (ref "U5") (pin "12") (pinfunction "TXD(P0.14)_12") (pintype "bidirectional"))
    )
    (net (code "46") (name "/V METER") (class "Default")
      (node (ref "R29") (pin "1") (pinfunction "1_1") (pintype "passive"))
      (node (ref "R30") (pin "2") (pinfunction "2_2") (pintype "passive"))
      (node (ref "U1") (pin "35") (pinfunction "PB1_35") (pintype "bidirectional"))
    )
    (net (code "47") (name "/VCAP1") (class "Default")
      (node (ref "C4") (pin "2") (pinfunction "2_2") (pintype "passive"))
      (node (ref "U1") (pin "48") (pinfunction "VCAP_48") (pintype "power_in"))
    )
    (net (code "48") (name "/VCAP2") (class "Default")
      (node (ref "C5") (pin "2") (pinfunction "2_2") (pintype "passive"))
      (node (ref "U1") (pin "73") (pinfunction "VCAP_73") (pintype "power_in"))
    )
    (net (code "49") (name "/VCP M1") (class "Default")
      (node (ref "C18") (pin "2") (pinfunction "2_2") (pintype "passive"))
      (node (ref "U3") (pin "12") (pinfunction "VCP_12") (pintype "power_in"))
    )
    (net (code "50") (name "/VCP M2") (class "Default")
      (node (ref "C24") (pin "2") (pinfunction "2_2") (pintype "passive"))
      (node (ref "U4") (pin "12") (pinfunction "VCP_12") (pintype "power_in"))
    )
    (net (code "51") (name "/VREF M1") (class "Default")
      (node (ref "C19") (pin "2") (pinfunction "2_2") (pintype "passive"))
      (node (ref "R6") (pin "1") (pinfunction "1_1") (pintype "passive"))
      (node (ref "U3") (pin "5") (pinfunction "VREF_5") (pintype "input"))
    )
    (net (code "52") (name "/VREF M2") (class "Default")
      (node (ref "C20") (pin "2") (pinfunction "2_2") (pintype "passive"))
      (node (ref "R8") (pin "1") (pinfunction "1_1") (pintype "passive"))
      (node (ref "U4") (pin "5") (pinfunction "VREF_5") (pintype "input"))
    )
    (net (code "53") (name "/W{slash}S") (class "Default")
      (node (ref "U1") (pin "63") (pinfunction "PC6_63") (pintype "bidirectional"))
      (node (ref "U5") (pin "7") (pinfunction "WKP(P0.05)_7") (pintype "bidirectional"))
    )
    (net (code "54") (name "/XSHUT1") (class "Default")
      (node (ref "P1") (pin "6") (pinfunction "6_6") (pintype "passive"))
      (node (ref "U1") (pin "97") (pinfunction "PE0_97") (pintype "bidirectional"))
    )
    (net (code "55") (name "/XSHUT2") (class "Default")
      (node (ref "P2") (pin "6") (pinfunction "6_6") (pintype "passive"))
      (node (ref "U1") (pin "98") (pinfunction "PE1_98") (pintype "bidirectional"))
    )
    (net (code "56") (name "/XSHUT3") (class "Default")
      (node (ref "P3") (pin "6") (pinfunction "6_6") (pintype "passive"))
      (node (ref "U1") (pin "1") (pinfunction "PE2_1") (pintype "bidirectional"))
    )
    (net (code "57") (name "/XSHUT4") (class "Default")
      (node (ref "P4") (pin "6") (pinfunction "6_6") (pintype "passive"))
      (node (ref "U1") (pin "3") (pinfunction "PE4_3") (pintype "bidirectional"))
    )
    (net (code "58") (name "/XSHUT5") (class "Default")
      (node (ref "P5") (pin "6") (pinfunction "6_6") (pintype "passive"))
      (node (ref "U1") (pin "4") (pinfunction "PE5_4") (pintype "bidirectional"))
    )
    (net (code "59") (name "3.3V") (class "Default")
      (node (ref "C10") (pin "2") (pinfunction "2_2") (pintype "passive"))
      (node (ref "C11") (pin "1") (pinfunction "1_1") (pintype "passive"))
      (node (ref "C14") (pin "2") (pinfunction "2_2") (pintype "passive"))
      (node (ref "C27") (pin "2") (pinfunction "2_2") (pintype "passive"))
      (node (ref "C29") (pin "2") (pinfunction "2_2") (pintype "passive"))
      (node (ref "C3") (pin "2") (pinfunction "2_2") (pintype "passive"))
      (node (ref "C30") (pin "2") (pinfunction "2_2") (pintype "passive"))
      (node (ref "C6") (pin "2") (pinfunction "2_2") (pintype "passive"))
      (node (ref "C7") (pin "2") (pinfunction "2_2") (pintype "passive"))
      (node (ref "C8") (pin "2") (pinfunction "2_2") (pintype "passive"))
      (node (ref "C9") (pin "2") (pinfunction "2_2") (pintype "passive"))
      (node (ref "FL1") (pin "2") (pinfunction "2_2") (pintype "passive"))
      (node (ref "FL2") (pin "2") (pinfunction "2_2") (pintype "passive"))
      (node (ref "J2") (pin "1") (pinfunction "1_1") (pintype "passive"))
      (node (ref "P1") (pin "1") (pinfunction "1_1") (pintype "passive"))
      (node (ref "P2") (pin "1") (pinfunction "1_1") (pintype "passive"))
      (node (ref "P3") (pin "1") (pinfunction "1_1") (pintype "passive"))
      (node (ref "P4") (pin "1") (pinfunction "1_1") (pintype "passive"))
      (node (ref "P5") (pin "1") (pinfunction "1_1") (pintype "passive"))
      (node (ref "P6") (pin "2") (pinfunction "2_2") (pintype "passive"))
      (node (ref "R10") (pin "1") (pinfunction "1_1") (pintype "passive"))
      (node (ref "R11") (pin "1") (pinfunction "1_1") (pintype "passive"))
      (node (ref "R12") (pin "2") (pinfunction "2_2") (pintype "passive"))
      (node (ref "R13") (pin "1") (pinfunction "1_1") (pintype "passive"))
      (node (ref "R14") (pin "1") (pinfunction "1_1") (pintype "passive"))
      (node (ref "R15") (pin "1") (pinfunction "1_1") (pintype "passive"))
      (node (ref "R17") (pin "2") (pinfunction "2_2") (pintype "passive"))
      (node (ref "R19") (pin "2") (pinfunction "2_2") (pintype "passive"))
      (node (ref "R2") (pin "2") (pinfunction "2_2") (pintype "passive"))
      (node (ref "R21") (pin "2") (pinfunction "2_2") (pintype "passive"))
      (node (ref "R22") (pin "2") (pinfunction "2_2") (pintype "passive"))
      (node (ref "R5") (pin "1") (pinfunction "1_1") (pintype "passive"))
      (node (ref "R7") (pin "1") (pinfunction "1_1") (pintype "passive"))
      (node (ref "S1") (pin "2") (pinfunction "2_2") (pintype "passive"))
      (node (ref "TP1") (pin "1") (pinfunction "1_1") (pintype "passive"))
      (node (ref "U1") (pin "100") (pinfunction "VDD_100") (pintype "power_in"))
      (node (ref "U1") (pin "11") (pinfunction "VDD_11") (pintype "power_in"))
      (node (ref "U1") (pin "27") (pinfunction "VDD_27") (pintype "power_in"))
      (node (ref "U1") (pin "50") (pinfunction "VDD_50") (pintype "power_in"))
      (node (ref "U1") (pin "6") (pinfunction "VBAT_6") (pintype "power_in"))
      (node (ref "U1") (pin "75") (pinfunction "VDD_75") (pintype "power_in"))
      (node (ref "U12") (pin "4") (pinfunction "VOUT_4") (pintype "output"))
      (node (ref "U12") (pin "5") (pinfunction "VOUT_5") (pintype "output"))
      (node (ref "U2") (pin "5") (pinfunction "VDDIO_5") (pintype "power_in"))
      (node (ref "U5") (pin "4") (pinfunction "VCC_4") (pintype "power_in"))
      (node (ref "U8") (pin "2") (pinfunction "VCC_IN_2") (pintype "power_in"))
    )
    (net (code "60") (name "7.4V") (class "Default")
      (node (ref "C13") (pin "2") (pinfunction "2_2") (pintype "passive"))
      (node (ref "C16") (pin "2") (pinfunction "2_2") (pintype "passive"))
      (node (ref "C17") (pin "1") (pinfunction "1_1") (pintype "passive"))
      (node (ref "C22") (pin "2") (pinfunction "2_2") (pintype "passive"))
      (node (ref "C23") (pin "1") (pinfunction "1_1") (pintype "passive"))
      (node (ref "C32") (pin "2") (pinfunction "2_2") (pintype "passive"))
      (node (ref "R29") (pin "2") (pinfunction "2_2") (pintype "passive"))
      (node (ref "TP3") (pin "1") (pinfunction "1_1") (pintype "passive"))
      (node (ref "U12") (pin "1") (pinfunction "EN_1") (pintype "input"))
      (node (ref "U12") (pin "2") (pinfunction "VIN_2") (pintype "input"))
      (node (ref "U3") (pin "11") (pinfunction "VM_11") (pintype "power_in"))
      (node (ref "U4") (pin "11") (pinfunction "VM_11") (pintype "power_in"))
      (node (ref "U9") (pin "3") (pinfunction "D_3") (pintype "passive"))
    )
    (net (code "61") (name "7.4V BAT") (class "Default")
      (node (ref "S2") (pin "1") (pinfunction "COM_1") (pintype "passive"))
      (node (ref "U9") (pin "2") (pinfunction "S_2") (pintype "passive"))
    )
    (net (code "62") (name "BAT") (class "Default")
      (node (ref "J1") (pin "1") (pinfunction "1_1") (pintype "passive"))
      (node (ref "S2") (pin "2") (pinfunction "NO_2") (pintype "passive"))
    )
    (net (code "63") (name "GND") (class "Default")
      (node (ref "C1") (pin "2") (pinfunction "2_2") (pintype "passive"))
      (node (ref "C10") (pin "1") (pinfunction "1_1") (pintype "passive"))
      (node (ref "C11") (pin "2") (pinfunction "2_2") (pintype "passive"))
      (node (ref "C12") (pin "1") (pinfunction "1_1") (pintype "passive"))
      (node (ref "C13") (pin "1") (pinfunction "1_1") (pintype "passive"))
      (node (ref "C14") (pin "1") (pinfunction "1_1") (pintype "passive"))
      (node (ref "C16") (pin "1") (pinfunction "1_1") (pintype "passive"))
      (node (ref "C17") (pin "2") (pinfunction "2_2") (pintype "passive"))
      (node (ref "C19") (pin "1") (pinfunction "1_1") (pintype "passive"))
      (node (ref "C2") (pin "2") (pinfunction "2_2") (pintype "passive"))
      (node (ref "C20") (pin "1") (pinfunction "1_1") (pintype "passive"))
      (node (ref "C22") (pin "1") (pinfunction "1_1") (pintype "passive"))
      (node (ref "C23") (pin "2") (pinfunction "2_2") (pintype "passive"))
      (node (ref "C25") (pin "1") (pinfunction "1_1") (pintype "passive"))
      (node (ref "C26") (pin "1") (pinfunction "1_1") (pintype "passive"))
      (node (ref "C27") (pin "1") (pinfunction "1_1") (pintype "passive"))
      (node (ref "C28") (pin "2") (pinfunction "2_2") (pintype "passive"))
      (node (ref "C29") (pin "1") (pinfunction "1_1") (pintype "passive"))
      (node (ref "C3") (pin "1") (pinfunction "1_1") (pintype "passive"))
      (node (ref "C30") (pin "1") (pinfunction "1_1") (pintype "passive"))
      (node (ref "C31") (pin "1") (pinfunction "1_1") (pintype "passive"))
      (node (ref "C32") (pin "1") (pinfunction "1_1") (pintype "passive"))
      (node (ref "C33") (pin "1") (pinfunction "1_1") (pintype "passive"))
      (node (ref "C34") (pin "1") (pinfunction "1_1") (pintype "passive"))
      (node (ref "C35") (pin "1") (pinfunction "1_1") (pintype "passive"))
      (node (ref "C4") (pin "1") (pinfunction "1_1") (pintype "passive"))
      (node (ref "C5") (pin "1") (pinfunction "1_1") (pintype "passive"))
      (node (ref "C6") (pin "1") (pinfunction "1_1") (pintype "passive"))
      (node (ref "C7") (pin "1") (pinfunction "1_1") (pintype "passive"))
      (node (ref "C8") (pin "1") (pinfunction "1_1") (pintype "passive"))
      (node (ref "C9") (pin "1") (pinfunction "1_1") (pintype "passive"))
      (node (ref "D2") (pin "C") (pinfunction "C_C") (pintype "passive"))
      (node (ref "D3") (pin "C") (pinfunction "C_C") (pintype "passive"))
      (node (ref "D4") (pin "C") (pinfunction "C_C") (pintype "passive"))
      (node (ref "D5") (pin "C") (pinfunction "C_C") (pintype "passive"))
      (node (ref "D6") (pin "C") (pinfunction "C_C") (pintype "passive"))
      (node (ref "D7") (pin "C") (pinfunction "C_C") (pintype "passive"))
      (node (ref "D8") (pin "C") (pinfunction "C_C") (pintype "passive"))
      (node (ref "J1") (pin "2") (pinfunction "2_2") (pintype "passive"))
      (node (ref "J2") (pin "10") (pinfunction "10_10") (pintype "passive"))
      (node (ref "J2") (pin "6") (pinfunction "6_6") (pintype "passive"))
      (node (ref "J2") (pin "8") (pinfunction "8_8") (pintype "passive"))
      (node (ref "P1") (pin "2") (pinfunction "2_2") (pintype "passive"))
      (node (ref "P2") (pin "2") (pinfunction "2_2") (pintype "passive"))
      (node (ref "P3") (pin "2") (pinfunction "2_2") (pintype "passive"))
      (node (ref "P4") (pin "2") (pinfunction "2_2") (pintype "passive"))
      (node (ref "P5") (pin "2") (pinfunction "2_2") (pintype "passive"))
      (node (ref "P6") (pin "1") (pinfunction "1_1") (pintype "passive"))
      (node (ref "Q1") (pin "E") (pinfunction "E_E") (pintype "passive"))
      (node (ref "Q2") (pin "E") (pinfunction "E_E") (pintype "passive"))
      (node (ref "Q3") (pin "E") (pinfunction "E_E") (pintype "passive"))
      (node (ref "R1") (pin "1") (pinfunction "1_1") (pintype "passive"))
      (node (ref "R26") (pin "2") (pinfunction "2_2") (pintype "passive"))
      (node (ref "R3") (pin "1") (pinfunction "1_1") (pintype "passive"))
      (node (ref "R30") (pin "1") (pinfunction "1_1") (pintype "passive"))
      (node (ref "R4") (pin "1") (pinfunction "1_1") (pintype "passive"))
      (node (ref "R9") (pin "1") (pinfunction "1_1") (pintype "passive"))
      (node (ref "S3") (pin "1") (pinfunction "1_1") (pintype "passive"))
      (node (ref "S4") (pin "1") (pinfunction "1_1") (pintype "passive"))
      (node (ref "TP2") (pin "1") (pinfunction "1_1") (pintype "passive"))
      (node (ref "U1") (pin "10") (pinfunction "VSS_10") (pintype "power_in"))
      (node (ref "U1") (pin "19") (pinfunction "VSSA_19") (pintype "power_in"))
      (node (ref "U1") (pin "26") (pinfunction "VSS_26") (pintype "power_in"))
      (node (ref "U1") (pin "49") (pinfunction "VSS_49") (pintype "power_in"))
      (node (ref "U1") (pin "74") (pinfunction "VSS_74") (pintype "power_in"))
      (node (ref "U1") (pin "99") (pinfunction "VSS_99") (pintype "power_in"))
      (node (ref "U12") (pin "10") (pinfunction "GND_10") (pintype "power_in"))
      (node (ref "U12") (pin "11") (pinfunction "GND_11") (pintype "power_in"))
      (node (ref "U12") (pin "12") (pinfunction "GND_12") (pintype "power_in"))
      (node (ref "U12") (pin "3") (pinfunction "GND_3") (pintype "power_in"))
      (node (ref "U12") (pin "9") (pinfunction "GND_9") (pintype "power_in"))
      (node (ref "U2") (pin "10") (pinfunction "RESV_10_10") (pintype "passive"))
      (node (ref "U2") (pin "11") (pinfunction "RESV_11_11") (pintype "passive"))
      (node (ref "U2") (pin "2") (pinfunction "RESV_2_2") (pintype "passive"))
      (node (ref "U2") (pin "3") (pinfunction "RESV_3_3") (pintype "passive"))
      (node (ref "U2") (pin "6") (pinfunction "GND_6") (pintype "power_in"))
      (node (ref "U2") (pin "7") (pinfunction "RESV_7_7") (pintype "passive"))
      (node (ref "U2") (pin "9") (pinfunction "INT2/FSYNC/CLKIN_9") (pintype "bidirectional"))
      (node (ref "U3") (pin "15") (pinfunction "GND_15") (pintype "power_in"))
      (node (ref "U3") (pin "16") (pinfunction "PMODE_16") (pintype "input"))
      (node (ref "U3") (pin "7") (pinfunction "IMODE_7") (pintype "input"))
      (node (ref "U3") (pin "9") (pinfunction "PGND_9") (pintype "power_in"))
      (node (ref "U4") (pin "15") (pinfunction "GND_15") (pintype "power_in"))
      (node (ref "U4") (pin "16") (pinfunction "PMODE_16") (pintype "input"))
      (node (ref "U4") (pin "7") (pinfunction "IMODE_7") (pintype "input"))
      (node (ref "U4") (pin "9") (pinfunction "PGND_9") (pintype "power_in"))
      (node (ref "U5") (pin "14") (pinfunction "GND_14") (pintype "power_in"))
      (node (ref "U5") (pin "5") (pinfunction "GND_5") (pintype "power_in"))
      (node (ref "U6") (pin "2") (pinfunction "C_2") (pintype "passive"))
      (node (ref "U6") (pin "4") (pinfunction "ET_4") (pintype "passive"))
      (node (ref "U7") (pin "2") (pinfunction "C_2") (pintype "passive"))
      (node (ref "U7") (pin "4") (pinfunction "ET_4") (pintype "passive"))
      (node (ref "U8") (pin "1") (pinfunction "GND_1") (pintype "power_in"))
    )
    (net (code "64") (name "Net-(D2-PadA)") (class "Default")
      (node (ref "D2") (pin "A") (pinfunction "A_A") (pintype "passive"))
      (node (ref "R16") (pin "1") (pinfunction "1_1") (pintype "passive"))
    )
    (net (code "65") (name "Net-(D3-PadA)") (class "Default")
      (node (ref "D3") (pin "A") (pinfunction "A_A") (pintype "passive"))
      (node (ref "R18") (pin "1") (pinfunction "1_1") (pintype "passive"))
    )
    (net (code "66") (name "Net-(D4-PadA)") (class "Default")
      (node (ref "D4") (pin "A") (pinfunction "A_A") (pintype "passive"))
      (node (ref "R20") (pin "1") (pinfunction "1_1") (pintype "passive"))
    )
    (net (code "67") (name "Net-(M1-+)") (class "Default")
      (node (ref "M1") (pin "1") (pinfunction "+_1") (pintype "passive"))
      (node (ref "U3") (pin "8") (pinfunction "OUT1_8") (pintype "output"))
    )
    (net (code "68") (name "Net-(M1--)") (class "Default")
      (node (ref "M1") (pin "2") (pinfunction "-_2") (pintype "passive"))
      (node (ref "U3") (pin "10") (pinfunction "OUT2_10") (pintype "output"))
    )
    (net (code "69") (name "Net-(M2-+)") (class "Default")
      (node (ref "M2") (pin "1") (pinfunction "+_1") (pintype "passive"))
      (node (ref "U4") (pin "8") (pinfunction "OUT1_8") (pintype "output"))
    )
    (net (code "70") (name "Net-(M2--)") (class "Default")
      (node (ref "M2") (pin "2") (pinfunction "-_2") (pintype "passive"))
      (node (ref "U4") (pin "10") (pinfunction "OUT2_10") (pintype "output"))
    )
    (net (code "71") (name "Net-(U1-PA0)") (class "Default")
      (node (ref "R31") (pin "1") (pinfunction "1_1") (pintype "passive"))
      (node (ref "U1") (pin "22") (pinfunction "PA0_22") (pintype "bidirectional"))
    )
    (net (code "72") (name "Net-(U1-PA1)") (class "Default")
      (node (ref "R32") (pin "1") (pinfunction "1_1") (pintype "passive"))
      (node (ref "U1") (pin "23") (pinfunction "PA1_23") (pintype "bidirectional"))
    )
    (net (code "73") (name "Net-(U1-PA2)") (class "Default")
      (node (ref "R33") (pin "1") (pinfunction "1_1") (pintype "passive"))
      (node (ref "U1") (pin "24") (pinfunction "PA2_24") (pintype "bidirectional"))
    )
    (net (code "74") (name "Net-(U1-VDDA)") (class "Default")
      (node (ref "C1") (pin "1") (pinfunction "1_1") (pintype "passive"))
      (node (ref "C2") (pin "1") (pinfunction "1_1") (pintype "passive"))
      (node (ref "FL1") (pin "1") (pinfunction "1_1") (pintype "passive"))
      (node (ref "U1") (pin "20") (pinfunction "VREF+_20") (pintype "power_in"))
      (node (ref "U1") (pin "21") (pinfunction "VDDA_21") (pintype "power_in"))
    )
    (net (code "75") (name "Net-(U2-VDD)") (class "Default")
      (node (ref "C25") (pin "2") (pinfunction "2_2") (pintype "passive"))
      (node (ref "C26") (pin "2") (pinfunction "2_2") (pintype "passive"))
      (node (ref "FL2") (pin "1") (pinfunction "1_1") (pintype "passive"))
      (node (ref "U2") (pin "8") (pinfunction "VDD_8") (pintype "power_in"))
    )
    (net (code "76") (name "Net-(U3-CPH)") (class "Default")
      (node (ref "C15") (pin "2") (pinfunction "2_2") (pintype "passive"))
      (node (ref "U3") (pin "13") (pinfunction "CPH_13") (pintype "power_in"))
    )
    (net (code "77") (name "Net-(U3-CPL)") (class "Default")
      (node (ref "C15") (pin "1") (pinfunction "1_1") (pintype "passive"))
      (node (ref "U3") (pin "14") (pinfunction "CPL_14") (pintype "power_in"))
    )
    (net (code "78") (name "Net-(U4-CPH)") (class "Default")
      (node (ref "C21") (pin "2") (pinfunction "2_2") (pintype "passive"))
      (node (ref "U4") (pin "13") (pinfunction "CPH_13") (pintype "power_in"))
    )
    (net (code "79") (name "Net-(U4-CPL)") (class "Default")
      (node (ref "C21") (pin "1") (pinfunction "1_1") (pintype "passive"))
      (node (ref "U4") (pin "14") (pinfunction "CPL_14") (pintype "power_in"))
    )
    (net (code "80") (name "Net-(U5-LINK(P0.16))") (class "Default")
      (node (ref "D1") (pin "C") (pinfunction "C_C") (pintype "passive"))
      (node (ref "U5") (pin "13") (pinfunction "LINK(P0.16)_13") (pintype "bidirectional"))
    )
    (net (code "81") (name "Net-(U6-A)") (class "Default")
      (node (ref "R14") (pin "2") (pinfunction "2_2") (pintype "passive"))
      (node (ref "U6") (pin "1") (pinfunction "A_1") (pintype "passive"))
    )
    (net (code "82") (name "Net-(U7-A)") (class "Default")
      (node (ref "R11") (pin "2") (pinfunction "2_2") (pintype "passive"))
      (node (ref "U7") (pin "1") (pinfunction "A_1") (pintype "passive"))
    )
    (net (code "83") (name "Net-(U9-G)") (class "Default")
      (node (ref "R26") (pin "1") (pinfunction "1_1") (pintype "passive"))
      (node (ref "U9") (pin "1") (pinfunction "G_1") (pintype "passive"))
    )
    (net (code "84") (name "Net-(U12-SS{slash}TR)") (class "Default")
      (node (ref "C12") (pin "2") (pinfunction "2_2") (pintype "passive"))
      (node (ref "U12") (pin "8") (pinfunction "SS/TR_8") (pintype "input"))
    )
    (net (code "85") (name "unconnected-(C18-Pad1)") (class "Default")
      (node (ref "C18") (pin "1") (pinfunction "1_1") (pintype "passive"))
    )
    (net (code "86") (name "unconnected-(C24-Pad1)") (class "Default")
      (node (ref "C24") (pin "1") (pinfunction "1_1") (pintype "passive"))
    )
    (net (code "87") (name "unconnected-(D1-PadA)") (class "Default")
      (node (ref "D1") (pin "A") (pinfunction "A_A") (pintype "passive"))
    )
    (net (code "88") (name "unconnected-(D5-PadA)") (class "Default")
      (node (ref "D5") (pin "A") (pinfunction "A_A") (pintype "passive"))
    )
    (net (code "89") (name "unconnected-(D6-PadA)") (class "Default")
      (node (ref "D6") (pin "A") (pinfunction "A_A") (pintype "passive"))
    )
    (net (code "90") (name "unconnected-(D7-PadA)") (class "Default")
      (node (ref "D7") (pin "A") (pinfunction "A_A") (pintype "passive"))
    )
    (net (code "91") (name "unconnected-(D8-PadA)") (class "Default")
      (node (ref "D8") (pin "A") (pinfunction "A_A") (pintype "passive"))
    )
    (net (code "92") (name "unconnected-(P1-Pad5)") (class "Default")
      (node (ref "P1") (pin "5") (pinfunction "5_5") (pintype "passive+no_connect"))
    )
    (net (code "93") (name "unconnected-(P2-Pad5)") (class "Default")
      (node (ref "P2") (pin "5") (pinfunction "5_5") (pintype "passive+no_connect"))
    )
    (net (code "94") (name "unconnected-(P3-Pad5)") (class "Default")
      (node (ref "P3") (pin "5") (pinfunction "5_5") (pintype "passive+no_connect"))
    )
    (net (code "95") (name "unconnected-(P4-Pad5)") (class "Default")
      (node (ref "P4") (pin "5") (pinfunction "5_5") (pintype "passive+no_connect"))
    )
    (net (code "96") (name "unconnected-(P5-Pad5)") (class "Default")
      (node (ref "P5") (pin "5") (pinfunction "5_5") (pintype "passive+no_connect"))
    )
    (net (code "97") (name "unconnected-(R12-Pad1)") (class "Default")
      (node (ref "R12") (pin "1") (pinfunction "1_1") (pintype "passive"))
    )
    (net (code "98") (name "unconnected-(R22-Pad1)") (class "Default")
      (node (ref "R22") (pin "1") (pinfunction "1_1") (pintype "passive"))
    )
    (net (code "99") (name "unconnected-(R23-Pad1)") (class "Default")
      (node (ref "R23") (pin "1") (pinfunction "1_1") (pintype "passive"))
    )
    (net (code "100") (name "unconnected-(R24-Pad1)") (class "Default")
      (node (ref "R24") (pin "1") (pinfunction "1_1") (pintype "passive"))
    )
    (net (code "101") (name "unconnected-(R25-Pad1)") (class "Default")
      (node (ref "R25") (pin "1") (pinfunction "1_1") (pintype "passive"))
    )
    (net (code "102") (name "unconnected-(U1-PA3-Pad25)") (class "Default")
      (node (ref "U1") (pin "25") (pinfunction "PA3_25") (pintype "bidirectional"))
    )
    (net (code "103") (name "unconnected-(U1-PA6-Pad30)") (class "Default")
      (node (ref "U1") (pin "30") (pinfunction "PA6_30") (pintype "bidirectional"))
    )
    (net (code "104") (name "unconnected-(U1-PA7-Pad31)") (class "Default")
      (node (ref "U1") (pin "31") (pinfunction "PA7_31") (pintype "bidirectional"))
    )
    (net (code "105") (name "unconnected-(U1-PA8-Pad67)") (class "Default")
      (node (ref "U1") (pin "67") (pinfunction "PA8_67") (pintype "bidirectional"))
    )
    (net (code "106") (name "unconnected-(U1-PA11-Pad70)") (class "Default")
      (node (ref "U1") (pin "70") (pinfunction "PA11_70") (pintype "bidirectional"))
    )
    (net (code "107") (name "unconnected-(U1-PA12-Pad71)") (class "Default")
      (node (ref "U1") (pin "71") (pinfunction "PA12_71") (pintype "bidirectional"))
    )
    (net (code "108") (name "unconnected-(U1-PA15-Pad77)") (class "Default")
      (node (ref "U1") (pin "77") (pinfunction "PA15_77") (pintype "bidirectional"))
    )
    (net (code "109") (name "unconnected-(U1-PB0-Pad34)") (class "Default")
      (node (ref "U1") (pin "34") (pinfunction "PB0_34") (pintype "bidirectional"))
    )
    (net (code "110") (name "unconnected-(U1-PB2-Pad36)") (class "Default")
      (node (ref "U1") (pin "36") (pinfunction "PB2_36") (pintype "bidirectional"))
    )
    (net (code "111") (name "unconnected-(U1-PB4-Pad90)") (class "Default")
      (node (ref "U1") (pin "90") (pinfunction "PB4_90") (pintype "bidirectional"))
    )
    (net (code "112") (name "unconnected-(U1-PB5-Pad91)") (class "Default")
      (node (ref "U1") (pin "91") (pinfunction "PB5_91") (pintype "bidirectional"))
    )
    (net (code "113") (name "unconnected-(U1-PB9-Pad96)") (class "Default")
      (node (ref "U1") (pin "96") (pinfunction "PB9_96") (pintype "bidirectional"))
    )
    (net (code "114") (name "unconnected-(U1-PB10-Pad46)") (class "Default")
      (node (ref "U1") (pin "46") (pinfunction "PB10_46") (pintype "bidirectional"))
    )
    (net (code "115") (name "unconnected-(U1-PB11-Pad47)") (class "Default")
      (node (ref "U1") (pin "47") (pinfunction "PB11_47") (pintype "bidirectional"))
    )
    (net (code "116") (name "unconnected-(U1-PB12-Pad51)") (class "Default")
      (node (ref "U1") (pin "51") (pinfunction "PB12_51") (pintype "bidirectional"))
    )
    (net (code "117") (name "unconnected-(U1-PC2_C-Pad17)") (class "Default")
      (node (ref "U1") (pin "17") (pinfunction "PC2_C_17") (pintype "bidirectional"))
    )
    (net (code "118") (name "unconnected-(U1-PC3_C-Pad18)") (class "Default")
      (node (ref "U1") (pin "18") (pinfunction "PC3_C_18") (pintype "bidirectional"))
    )
    (net (code "119") (name "unconnected-(U1-PC10-Pad78)") (class "Default")
      (node (ref "U1") (pin "78") (pinfunction "PC10_78") (pintype "bidirectional"))
    )
    (net (code "120") (name "unconnected-(U1-PC11-Pad79)") (class "Default")
      (node (ref "U1") (pin "79") (pinfunction "PC11_79") (pintype "bidirectional"))
    )
    (net (code "121") (name "unconnected-(U1-PC12-Pad80)") (class "Default")
      (node (ref "U1") (pin "80") (pinfunction "PC12_80") (pintype "bidirectional"))
    )
    (net (code "122") (name "unconnected-(U1-PC13-Pad7)") (class "Default")
      (node (ref "U1") (pin "7") (pinfunction "PC13_7") (pintype "bidirectional"))
    )
    (net (code "123") (name "unconnected-(U1-PC14-OSC32_IN-Pad8)") (class "Default")
      (node (ref "U1") (pin "8") (pinfunction "PC14-OSC32_IN_8") (pintype "bidirectional"))
    )
    (net (code "124") (name "unconnected-(U1-PC15-OSC32_OUT-Pad9)") (class "Default")
      (node (ref "U1") (pin "9") (pinfunction "PC15-OSC32_OUT_9") (pintype "bidirectional"))
    )
    (net (code "125") (name "unconnected-(U1-PD3-Pad84)") (class "Default")
      (node (ref "U1") (pin "84") (pinfunction "PD3_84") (pintype "bidirectional"))
    )
    (net (code "126") (name "unconnected-(U1-PD4-Pad85)") (class "Default")
      (node (ref "U1") (pin "85") (pinfunction "PD4_85") (pintype "bidirectional"))
    )
    (net (code "127") (name "unconnected-(U1-PD5-Pad86)") (class "Default")
      (node (ref "U1") (pin "86") (pinfunction "PD5_86") (pintype "bidirectional"))
    )
    (net (code "128") (name "unconnected-(U1-PD7-Pad88)") (class "Default")
      (node (ref "U1") (pin "88") (pinfunction "PD7_88") (pintype "bidirectional"))
    )
    (net (code "129") (name "unconnected-(U1-PD10-Pad57)") (class "Default")
      (node (ref "U1") (pin "57") (pinfunction "PD10_57") (pintype "bidirectional"))
    )
    (net (code "130") (name "unconnected-(U1-PD15-Pad62)") (class "Default")
      (node (ref "U1") (pin "62") (pinfunction "PD15_62") (pintype "bidirectional"))
    )
    (net (code "131") (name "unconnected-(U1-PE7-Pad37)") (class "Default")
      (node (ref "U1") (pin "37") (pinfunction "PE7_37") (pintype "bidirectional"))
    )
    (net (code "132") (name "unconnected-(U1-PE8-Pad38)") (class "Default")
      (node (ref "U1") (pin "38") (pinfunction "PE8_38") (pintype "bidirectional"))
    )
    (net (code "133") (name "unconnected-(U1-PH0-OSC_IN-Pad12)") (class "Default")
      (node (ref "U1") (pin "12") (pinfunction "PH0-OSC_IN_12") (pintype "bidirectional"))
    )
    (net (code "134") (name "unconnected-(U1-PH1-OSC_OUT-Pad13)") (class "Default")
      (node (ref "U1") (pin "13") (pinfunction "PH1-OSC_OUT_13") (pintype "bidirectional"))
    )
    (net (code "135") (name "unconnected-(U5-P0.00-Pad8)") (class "Default")
      (node (ref "U5") (pin "8") (pinfunction "P0.00_8") (pintype "bidirectional+no_connect"))
    )
    (net (code "136") (name "unconnected-(U5-P0.01-Pad10)") (class "Default")
      (node (ref "U5") (pin "10") (pinfunction "P0.01_10") (pintype "bidirectional+no_connect"))
    )
    (net (code "137") (name "unconnected-(U5-SWCLK-Pad2)") (class "Default")
      (node (ref "U5") (pin "2") (pinfunction "SWCLK_2") (pintype "bidirectional+no_connect"))
    )
    (net (code "138") (name "unconnected-(U5-SWDIO-Pad1)") (class "Default")
      (node (ref "U5") (pin "1") (pinfunction "SWDIO_1") (pintype "bidirectional+no_connect"))
    )
    (net (code "139") (name "unconnected-(U12-PG-Pad7)") (class "Default")
      (node (ref "U12") (pin "7") (pinfunction "PG_7") (pintype "output+no_connect"))
    )
  )
)
